# S206D.net
KiCad netlist of a schematic drawn in EAGLE
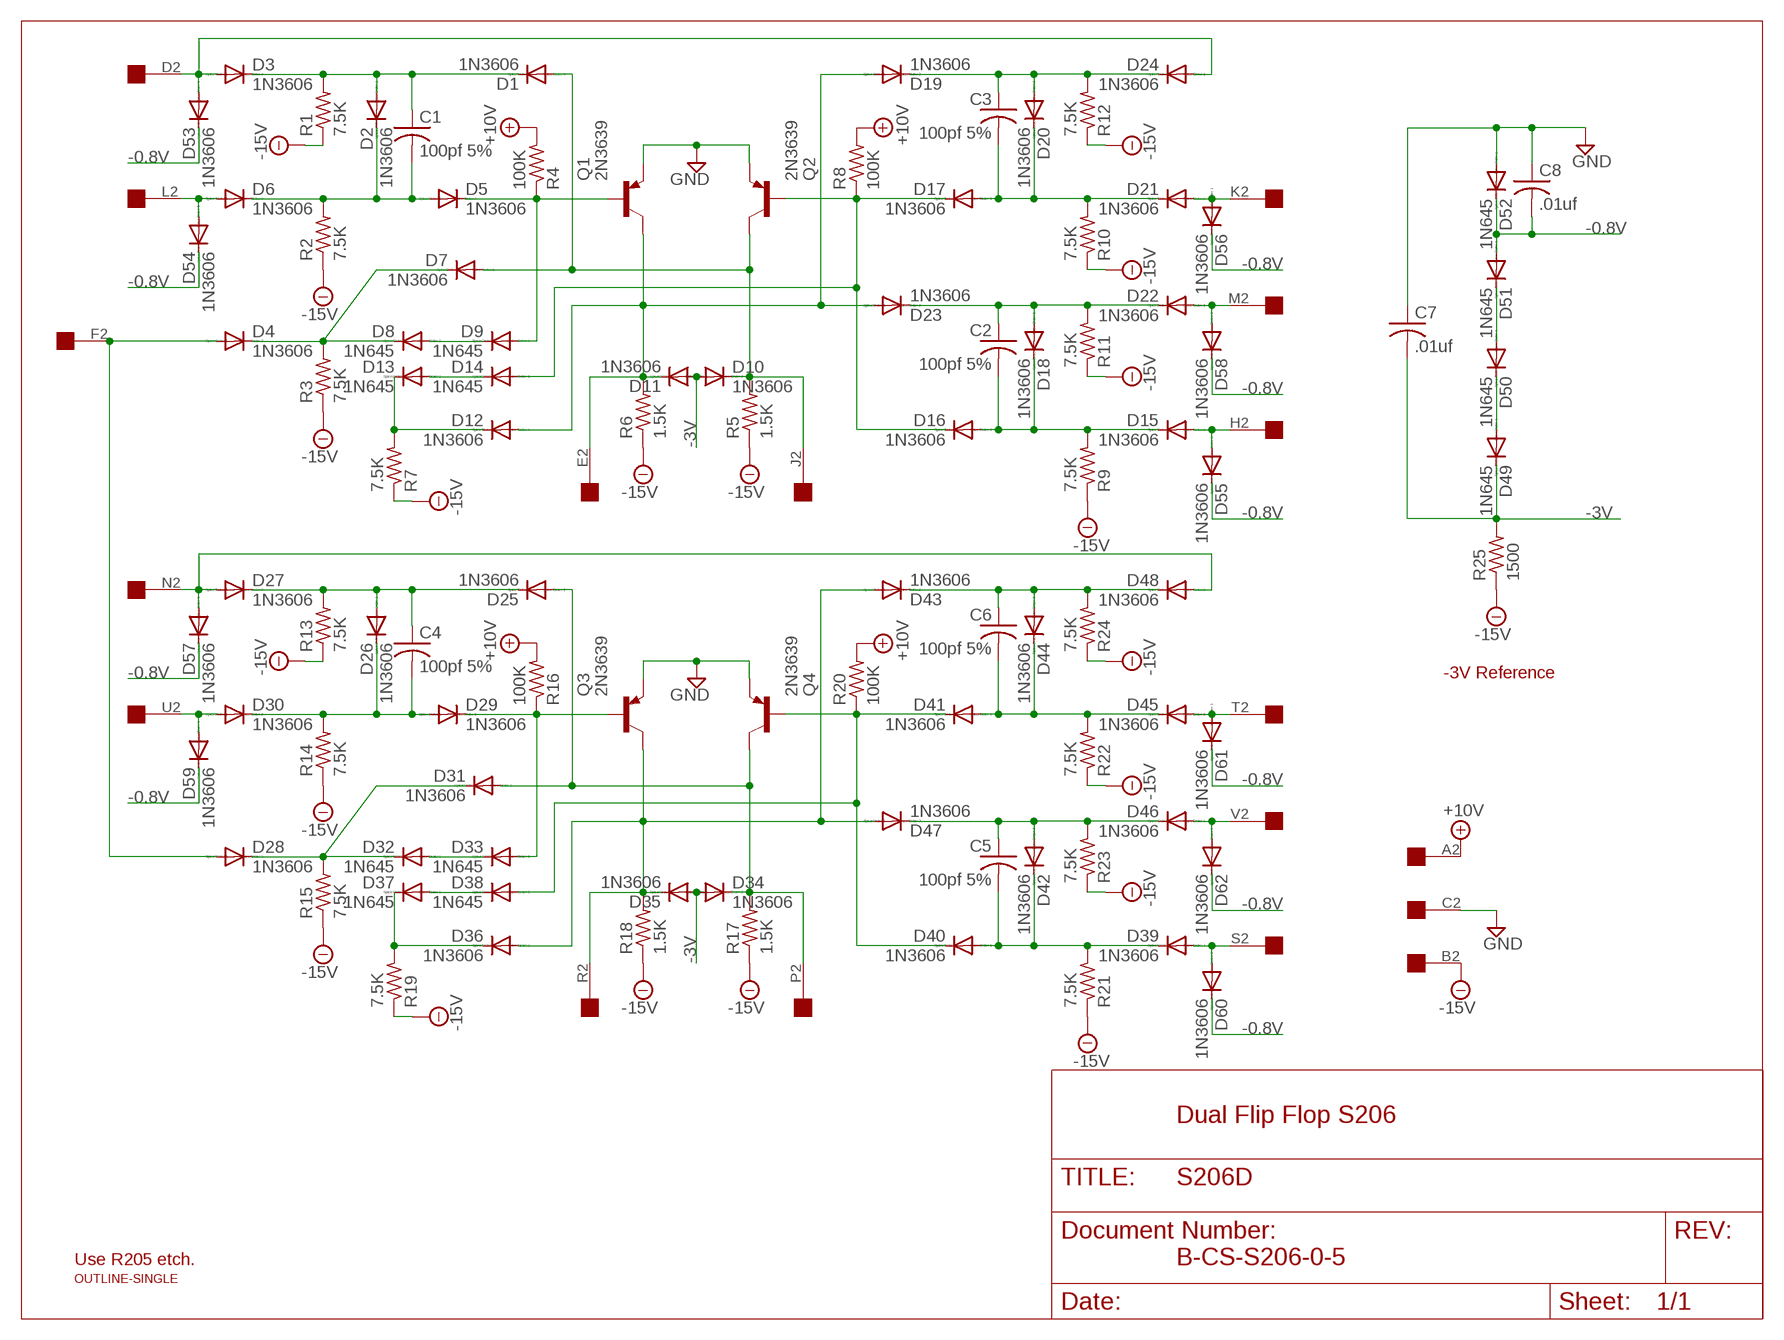
[diagram p0: schematic, sheet 1]

(export (version "E")
  (design (tool "Eeschema 10.0.6"))
  (components
    (comp (ref "C1")
      (value "100pf 5%")
      (footprint "eagle-import:C050-025X075")
      (libsource (lib "eagle-import") (part "C-US050-025X075"))
    )
    (comp (ref "C2")
      (value "100pf 5%")
      (footprint "eagle-import:C050-025X075")
      (libsource (lib "eagle-import") (part "C-US050-025X075"))
    )
    (comp (ref "C3")
      (value "100pf 5%")
      (footprint "eagle-import:C050-025X075")
      (libsource (lib "eagle-import") (part "C-US050-025X075"))
    )
    (comp (ref "C4")
      (value "100pf 5%")
      (footprint "eagle-import:C050-025X075")
      (libsource (lib "eagle-import") (part "C-US050-025X075"))
    )
    (comp (ref "C5")
      (value "100pf 5%")
      (footprint "eagle-import:C050-025X075")
      (libsource (lib "eagle-import") (part "C-US050-025X075"))
    )
    (comp (ref "C6")
      (value "100pf 5%")
      (footprint "eagle-import:C050-025X075")
      (libsource (lib "eagle-import") (part "C-US050-025X075"))
    )
    (comp (ref "C7")
      (value ".01uf")
      (footprint "eagle-import:C050-025X075")
      (libsource (lib "eagle-import") (part "C-US050-025X075"))
    )
    (comp (ref "C8")
      (value ".01uf")
      (footprint "eagle-import:C050-025X075")
      (libsource (lib "eagle-import") (part "C-US050-025X075"))
    )
    (comp (ref "D1")
      (value "1N3606")
      (footprint "eagle-import:DO35-10")
      (libsource (lib "eagle-import") (part "1N4148DO35-10"))
    )
    (comp (ref "D2")
      (value "1N3606")
      (footprint "eagle-import:DO35-10")
      (libsource (lib "eagle-import") (part "1N4148DO35-10"))
    )
    (comp (ref "D3")
      (value "1N3606")
      (footprint "eagle-import:DO35-10")
      (libsource (lib "eagle-import") (part "1N4148DO35-10"))
    )
    (comp (ref "D4")
      (value "1N3606")
      (footprint "eagle-import:DO35-10")
      (libsource (lib "eagle-import") (part "1N4148DO35-10"))
    )
    (comp (ref "D5")
      (value "1N3606")
      (footprint "eagle-import:DO35-10")
      (libsource (lib "eagle-import") (part "1N4148DO35-10"))
    )
    (comp (ref "D6")
      (value "1N3606")
      (footprint "eagle-import:DO35-10")
      (libsource (lib "eagle-import") (part "1N4148DO35-10"))
    )
    (comp (ref "D7")
      (value "1N3606")
      (footprint "eagle-import:DO35-10")
      (libsource (lib "eagle-import") (part "1N4148DO35-10"))
    )
    (comp (ref "D8")
      (value "1N645")
      (footprint "eagle-import:DO35-10")
      (libsource (lib "eagle-import") (part "1N4148DO35-10"))
    )
    (comp (ref "D9")
      (value "1N645")
      (footprint "eagle-import:DO35-10")
      (libsource (lib "eagle-import") (part "1N4148DO35-10"))
    )
    (comp (ref "D10")
      (value "1N3606")
      (footprint "eagle-import:DO35-10")
      (libsource (lib "eagle-import") (part "1N4148DO35-10"))
    )
    (comp (ref "D11")
      (value "1N3606")
      (footprint "eagle-import:DO35-10")
      (libsource (lib "eagle-import") (part "1N4148DO35-10"))
    )
    (comp (ref "D12")
      (value "1N3606")
      (footprint "eagle-import:DO35-10")
      (libsource (lib "eagle-import") (part "1N4148DO35-10"))
    )
    (comp (ref "D13")
      (value "1N645")
      (footprint "eagle-import:DO35-10")
      (libsource (lib "eagle-import") (part "1N4148DO35-10"))
    )
    (comp (ref "D14")
      (value "1N645")
      (footprint "eagle-import:DO35-10")
      (libsource (lib "eagle-import") (part "1N4148DO35-10"))
    )
    (comp (ref "D15")
      (value "1N3606")
      (footprint "eagle-import:DO35-10")
      (libsource (lib "eagle-import") (part "1N4148DO35-10"))
    )
    (comp (ref "D16")
      (value "1N3606")
      (footprint "eagle-import:DO35-10")
      (libsource (lib "eagle-import") (part "1N4148DO35-10"))
    )
    (comp (ref "D17")
      (value "1N3606")
      (footprint "eagle-import:DO35-10")
      (libsource (lib "eagle-import") (part "1N4148DO35-10"))
    )
    (comp (ref "D18")
      (value "1N3606")
      (footprint "eagle-import:DO35-10")
      (libsource (lib "eagle-import") (part "1N4148DO35-10"))
    )
    (comp (ref "D19")
      (value "1N3606")
      (footprint "eagle-import:DO35-10")
      (libsource (lib "eagle-import") (part "1N4148DO35-10"))
    )
    (comp (ref "D20")
      (value "1N3606")
      (footprint "eagle-import:DO35-10")
      (libsource (lib "eagle-import") (part "1N4148DO35-10"))
    )
    (comp (ref "D21")
      (value "1N3606")
      (footprint "eagle-import:DO35-10")
      (libsource (lib "eagle-import") (part "1N4148DO35-10"))
    )
    (comp (ref "D22")
      (value "1N3606")
      (footprint "eagle-import:DO35-10")
      (libsource (lib "eagle-import") (part "1N4148DO35-10"))
    )
    (comp (ref "D23")
      (value "1N3606")
      (footprint "eagle-import:DO35-10")
      (libsource (lib "eagle-import") (part "1N4148DO35-10"))
    )
    (comp (ref "D24")
      (value "1N3606")
      (footprint "eagle-import:DO35-10")
      (libsource (lib "eagle-import") (part "1N4148DO35-10"))
    )
    (comp (ref "D25")
      (value "1N3606")
      (footprint "eagle-import:DO35-10")
      (libsource (lib "eagle-import") (part "1N4148DO35-10"))
    )
    (comp (ref "D26")
      (value "1N3606")
      (footprint "eagle-import:DO35-10")
      (libsource (lib "eagle-import") (part "1N4148DO35-10"))
    )
    (comp (ref "D27")
      (value "1N3606")
      (footprint "eagle-import:DO35-10")
      (libsource (lib "eagle-import") (part "1N4148DO35-10"))
    )
    (comp (ref "D28")
      (value "1N3606")
      (footprint "eagle-import:DO35-10")
      (libsource (lib "eagle-import") (part "1N4148DO35-10"))
    )
    (comp (ref "D29")
      (value "1N3606")
      (footprint "eagle-import:DO35-10")
      (libsource (lib "eagle-import") (part "1N4148DO35-10"))
    )
    (comp (ref "D30")
      (value "1N3606")
      (footprint "eagle-import:DO35-10")
      (libsource (lib "eagle-import") (part "1N4148DO35-10"))
    )
    (comp (ref "D31")
      (value "1N3606")
      (footprint "eagle-import:DO35-10")
      (libsource (lib "eagle-import") (part "1N4148DO35-10"))
    )
    (comp (ref "D32")
      (value "1N645")
      (footprint "eagle-import:DO35-10")
      (libsource (lib "eagle-import") (part "1N4148DO35-10"))
    )
    (comp (ref "D33")
      (value "1N645")
      (footprint "eagle-import:DO35-10")
      (libsource (lib "eagle-import") (part "1N4148DO35-10"))
    )
    (comp (ref "D34")
      (value "1N3606")
      (footprint "eagle-import:DO35-10")
      (libsource (lib "eagle-import") (part "1N4148DO35-10"))
    )
    (comp (ref "D35")
      (value "1N3606")
      (footprint "eagle-import:DO35-10")
      (libsource (lib "eagle-import") (part "1N4148DO35-10"))
    )
    (comp (ref "D36")
      (value "1N3606")
      (footprint "eagle-import:DO35-10")
      (libsource (lib "eagle-import") (part "1N4148DO35-10"))
    )
    (comp (ref "D37")
      (value "1N645")
      (footprint "eagle-import:DO35-10")
      (libsource (lib "eagle-import") (part "1N4148DO35-10"))
    )
    (comp (ref "D38")
      (value "1N645")
      (footprint "eagle-import:DO35-10")
      (libsource (lib "eagle-import") (part "1N4148DO35-10"))
    )
    (comp (ref "D39")
      (value "1N3606")
      (footprint "eagle-import:DO35-10")
      (libsource (lib "eagle-import") (part "1N4148DO35-10"))
    )
    (comp (ref "D40")
      (value "1N3606")
      (footprint "eagle-import:DO35-10")
      (libsource (lib "eagle-import") (part "1N4148DO35-10"))
    )
    (comp (ref "D41")
      (value "1N3606")
      (footprint "eagle-import:DO35-10")
      (libsource (lib "eagle-import") (part "1N4148DO35-10"))
    )
    (comp (ref "D42")
      (value "1N3606")
      (footprint "eagle-import:DO35-10")
      (libsource (lib "eagle-import") (part "1N4148DO35-10"))
    )
    (comp (ref "D43")
      (value "1N3606")
      (footprint "eagle-import:DO35-10")
      (libsource (lib "eagle-import") (part "1N4148DO35-10"))
    )
    (comp (ref "D44")
      (value "1N3606")
      (footprint "eagle-import:DO35-10")
      (libsource (lib "eagle-import") (part "1N4148DO35-10"))
    )
    (comp (ref "D45")
      (value "1N3606")
      (footprint "eagle-import:DO35-10")
      (libsource (lib "eagle-import") (part "1N4148DO35-10"))
    )
    (comp (ref "D46")
      (value "1N3606")
      (footprint "eagle-import:DO35-10")
      (libsource (lib "eagle-import") (part "1N4148DO35-10"))
    )
    (comp (ref "D47")
      (value "1N3606")
      (footprint "eagle-import:DO35-10")
      (libsource (lib "eagle-import") (part "1N4148DO35-10"))
    )
    (comp (ref "D48")
      (value "1N3606")
      (footprint "eagle-import:DO35-10")
      (libsource (lib "eagle-import") (part "1N4148DO35-10"))
    )
    (comp (ref "D49")
      (value "1N645")
      (footprint "eagle-import:DO35-10")
      (libsource (lib "eagle-import") (part "1N4148DO35-10"))
    )
    (comp (ref "D50")
      (value "1N645")
      (footprint "eagle-import:DO35-10")
      (libsource (lib "eagle-import") (part "1N4148DO35-10"))
    )
    (comp (ref "D51")
      (value "1N645")
      (footprint "eagle-import:DO35-10")
      (libsource (lib "eagle-import") (part "1N4148DO35-10"))
    )
    (comp (ref "D52")
      (value "1N645")
      (footprint "eagle-import:DO35-10")
      (libsource (lib "eagle-import") (part "1N4148DO35-10"))
    )
    (comp (ref "D53")
      (value "1N3606")
      (footprint "eagle-import:DO35-10")
      (libsource (lib "eagle-import") (part "1N4148DO35-10"))
    )
    (comp (ref "D54")
      (value "1N3606")
      (footprint "eagle-import:DO35-10")
      (libsource (lib "eagle-import") (part "1N4148DO35-10"))
    )
    (comp (ref "D55")
      (value "1N3606")
      (footprint "eagle-import:DO35-10")
      (libsource (lib "eagle-import") (part "1N4148DO35-10"))
    )
    (comp (ref "D56")
      (value "1N3606")
      (footprint "eagle-import:DO35-10")
      (libsource (lib "eagle-import") (part "1N4148DO35-10"))
    )
    (comp (ref "D57")
      (value "1N3606")
      (footprint "eagle-import:DO35-10")
      (libsource (lib "eagle-import") (part "1N4148DO35-10"))
    )
    (comp (ref "D58")
      (value "1N3606")
      (footprint "eagle-import:DO35-10")
      (libsource (lib "eagle-import") (part "1N4148DO35-10"))
    )
    (comp (ref "D59")
      (value "1N3606")
      (footprint "eagle-import:DO35-10")
      (libsource (lib "eagle-import") (part "1N4148DO35-10"))
    )
    (comp (ref "D60")
      (value "1N3606")
      (footprint "eagle-import:DO35-10")
      (libsource (lib "eagle-import") (part "1N4148DO35-10"))
    )
    (comp (ref "D61")
      (value "1N3606")
      (footprint "eagle-import:DO35-10")
      (libsource (lib "eagle-import") (part "1N4148DO35-10"))
    )
    (comp (ref "D62")
      (value "1N3606")
      (footprint "eagle-import:DO35-10")
      (libsource (lib "eagle-import") (part "1N4148DO35-10"))
    )
    (comp (ref "Q1")
      (value "2N3639")
      (footprint "eagle-import:TO39")
      (libsource (lib "eagle-import") (part "2N3637"))
    )
    (comp (ref "Q2")
      (value "2N3639")
      (footprint "eagle-import:TO39")
      (libsource (lib "eagle-import") (part "2N3637"))
    )
    (comp (ref "Q3")
      (value "2N3639")
      (footprint "eagle-import:TO39")
      (libsource (lib "eagle-import") (part "2N3637"))
    )
    (comp (ref "Q4")
      (value "2N3639")
      (footprint "eagle-import:TO39")
      (libsource (lib "eagle-import") (part "2N3637"))
    )
    (comp (ref "R1")
      (value "7.5K")
      (footprint "eagle-import:0207_10")
      (libsource (lib "eagle-import") (part "R-US_0207/10"))
    )
    (comp (ref "R2")
      (value "7.5K")
      (footprint "eagle-import:0207_10")
      (libsource (lib "eagle-import") (part "R-US_0207/10"))
    )
    (comp (ref "R3")
      (value "7.5K")
      (footprint "eagle-import:0207_10")
      (libsource (lib "eagle-import") (part "R-US_0207/10"))
    )
    (comp (ref "R4")
      (value "100K")
      (footprint "eagle-import:0207_10")
      (libsource (lib "eagle-import") (part "R-US_0207/10"))
    )
    (comp (ref "R5")
      (value "1.5K")
      (footprint "eagle-import:0207_10")
      (libsource (lib "eagle-import") (part "R-US_0207/10"))
    )
    (comp (ref "R6")
      (value "1.5K")
      (footprint "eagle-import:0207_10")
      (libsource (lib "eagle-import") (part "R-US_0207/10"))
    )
    (comp (ref "R7")
      (value "7.5K")
      (footprint "eagle-import:0207_10")
      (libsource (lib "eagle-import") (part "R-US_0207/10"))
    )
    (comp (ref "R8")
      (value "100K")
      (footprint "eagle-import:0207_10")
      (libsource (lib "eagle-import") (part "R-US_0207/10"))
    )
    (comp (ref "R9")
      (value "7.5K")
      (footprint "eagle-import:0207_10")
      (libsource (lib "eagle-import") (part "R-US_0207/10"))
    )
    (comp (ref "R10")
      (value "7.5K")
      (footprint "eagle-import:0207_10")
      (libsource (lib "eagle-import") (part "R-US_0207/10"))
    )
    (comp (ref "R11")
      (value "7.5K")
      (footprint "eagle-import:0207_10")
      (libsource (lib "eagle-import") (part "R-US_0207/10"))
    )
    (comp (ref "R12")
      (value "7.5K")
      (footprint "eagle-import:0207_10")
      (libsource (lib "eagle-import") (part "R-US_0207/10"))
    )
    (comp (ref "R13")
      (value "7.5K")
      (footprint "eagle-import:0207_10")
      (libsource (lib "eagle-import") (part "R-US_0207/10"))
    )
    (comp (ref "R14")
      (value "7.5K")
      (footprint "eagle-import:0207_10")
      (libsource (lib "eagle-import") (part "R-US_0207/10"))
    )
    (comp (ref "R15")
      (value "7.5K")
      (footprint "eagle-import:0207_10")
      (libsource (lib "eagle-import") (part "R-US_0207/10"))
    )
    (comp (ref "R16")
      (value "100K")
      (footprint "eagle-import:0207_10")
      (libsource (lib "eagle-import") (part "R-US_0207/10"))
    )
    (comp (ref "R17")
      (value "1.5K")
      (footprint "eagle-import:0207_10")
      (libsource (lib "eagle-import") (part "R-US_0207/10"))
    )
    (comp (ref "R18")
      (value "1.5K")
      (footprint "eagle-import:0207_10")
      (libsource (lib "eagle-import") (part "R-US_0207/10"))
    )
    (comp (ref "R19")
      (value "7.5K")
      (footprint "eagle-import:0207_10")
      (libsource (lib "eagle-import") (part "R-US_0207/10"))
    )
    (comp (ref "R20")
      (value "100K")
      (footprint "eagle-import:0207_10")
      (libsource (lib "eagle-import") (part "R-US_0207/10"))
    )
    (comp (ref "R21")
      (value "7.5K")
      (footprint "eagle-import:0207_10")
      (libsource (lib "eagle-import") (part "R-US_0207/10"))
    )
    (comp (ref "R22")
      (value "7.5K")
      (footprint "eagle-import:0207_10")
      (libsource (lib "eagle-import") (part "R-US_0207/10"))
    )
    (comp (ref "R23")
      (value "7.5K")
      (footprint "eagle-import:0207_10")
      (libsource (lib "eagle-import") (part "R-US_0207/10"))
    )
    (comp (ref "R24")
      (value "7.5K")
      (footprint "eagle-import:0207_10")
      (libsource (lib "eagle-import") (part "R-US_0207/10"))
    )
    (comp (ref "R25")
      (value "1500")
      (footprint "eagle-import:0207_10")
      (libsource (lib "eagle-import") (part "R-US_0207/10"))
    )
    (comp (ref "U$1")
      (value "OUTLINE-SINGLE")
      (footprint "eagle-import:SINGLE")
      (libsource (lib "eagle-import") (part "OUTLINE-SINGLE"))
    )
    (comp (ref "U$2")
      (value "EDGE-1")
      (footprint "eagle-import:EDGE-CON1")
      (libsource (lib "eagle-import") (part "EDGE-1"))
    )
  )
  (nets
    (net (code "1") (name "+10V") (class "Default")
      (node (ref "R16") (pin "2") (pinfunction "2_2") (pintype "passive"))
      (node (ref "R20") (pin "2") (pinfunction "2_2") (pintype "passive"))
      (node (ref "R4") (pin "2") (pinfunction "2_2") (pintype "passive"))
      (node (ref "R8") (pin "2") (pinfunction "2_2") (pintype "passive"))
      (node (ref "U$2") (pin "A2") (pinfunction "1_A2") (pintype "bidirectional"))
    )
    (net (code "2") (name "-15V") (class "Default")
      (node (ref "R1") (pin "1") (pinfunction "1_1") (pintype "passive"))
      (node (ref "R10") (pin "1") (pinfunction "1_1") (pintype "passive"))
      (node (ref "R11") (pin "1") (pinfunction "1_1") (pintype "passive"))
      (node (ref "R12") (pin "1") (pinfunction "1_1") (pintype "passive"))
      (node (ref "R13") (pin "1") (pinfunction "1_1") (pintype "passive"))
      (node (ref "R14") (pin "1") (pinfunction "1_1") (pintype "passive"))
      (node (ref "R15") (pin "1") (pinfunction "1_1") (pintype "passive"))
      (node (ref "R17") (pin "1") (pinfunction "1_1") (pintype "passive"))
      (node (ref "R18") (pin "1") (pinfunction "1_1") (pintype "passive"))
      (node (ref "R19") (pin "1") (pinfunction "1_1") (pintype "passive"))
      (node (ref "R2") (pin "1") (pinfunction "1_1") (pintype "passive"))
      (node (ref "R21") (pin "1") (pinfunction "1_1") (pintype "passive"))
      (node (ref "R22") (pin "1") (pinfunction "1_1") (pintype "passive"))
      (node (ref "R23") (pin "1") (pinfunction "1_1") (pintype "passive"))
      (node (ref "R24") (pin "1") (pinfunction "1_1") (pintype "passive"))
      (node (ref "R25") (pin "1") (pinfunction "1_1") (pintype "passive"))
      (node (ref "R3") (pin "1") (pinfunction "1_1") (pintype "passive"))
      (node (ref "R5") (pin "1") (pinfunction "1_1") (pintype "passive"))
      (node (ref "R6") (pin "1") (pinfunction "1_1") (pintype "passive"))
      (node (ref "R7") (pin "1") (pinfunction "1_1") (pintype "passive"))
      (node (ref "R9") (pin "1") (pinfunction "1_1") (pintype "passive"))
      (node (ref "U$2") (pin "B2") (pinfunction "1_B2") (pintype "bidirectional"))
    )
    (net (code "3") (name "/-0.8V") (class "Default")
      (node (ref "C8") (pin "2") (pinfunction "2_2") (pintype "passive"))
      (node (ref "D51") (pin "A") (pinfunction "A_A") (pintype "passive"))
      (node (ref "D52") (pin "C") (pinfunction "C_C") (pintype "passive"))
      (node (ref "D53") (pin "C") (pinfunction "C_C") (pintype "passive"))
      (node (ref "D54") (pin "C") (pinfunction "C_C") (pintype "passive"))
      (node (ref "D55") (pin "C") (pinfunction "C_C") (pintype "passive"))
      (node (ref "D56") (pin "C") (pinfunction "C_C") (pintype "passive"))
      (node (ref "D57") (pin "C") (pinfunction "C_C") (pintype "passive"))
      (node (ref "D58") (pin "C") (pinfunction "C_C") (pintype "passive"))
      (node (ref "D59") (pin "C") (pinfunction "C_C") (pintype "passive"))
      (node (ref "D60") (pin "C") (pinfunction "C_C") (pintype "passive"))
      (node (ref "D61") (pin "C") (pinfunction "C_C") (pintype "passive"))
      (node (ref "D62") (pin "C") (pinfunction "C_C") (pintype "passive"))
    )
    (net (code "4") (name "/-3V") (class "Default")
      (node (ref "C7") (pin "2") (pinfunction "2_2") (pintype "passive"))
      (node (ref "D10") (pin "A") (pinfunction "A_A") (pintype "passive"))
      (node (ref "D11") (pin "A") (pinfunction "A_A") (pintype "passive"))
      (node (ref "D34") (pin "A") (pinfunction "A_A") (pintype "passive"))
      (node (ref "D35") (pin "A") (pinfunction "A_A") (pintype "passive"))
      (node (ref "D49") (pin "C") (pinfunction "C_C") (pintype "passive"))
      (node (ref "R25") (pin "2") (pinfunction "2_2") (pintype "passive"))
    )
    (net (code "5") (name "GND") (class "Default")
      (node (ref "C7") (pin "1") (pinfunction "1_1") (pintype "passive"))
      (node (ref "C8") (pin "1") (pinfunction "1_1") (pintype "passive"))
      (node (ref "D52") (pin "A") (pinfunction "A_A") (pintype "passive"))
      (node (ref "Q1") (pin "1") (pinfunction "E_1") (pintype "passive"))
      (node (ref "Q2") (pin "1") (pinfunction "E_1") (pintype "passive"))
      (node (ref "Q3") (pin "1") (pinfunction "E_1") (pintype "passive"))
      (node (ref "Q4") (pin "1") (pinfunction "E_1") (pintype "passive"))
      (node (ref "U$2") (pin "C2") (pinfunction "1_C2") (pintype "bidirectional"))
    )
    (net (code "6") (name "Net-(C1-Pad1)") (class "Default")
      (node (ref "C1") (pin "1") (pinfunction "1_1") (pintype "passive"))
      (node (ref "D1") (pin "C") (pinfunction "C_C") (pintype "passive"))
      (node (ref "D2") (pin "A") (pinfunction "A_A") (pintype "passive"))
      (node (ref "D3") (pin "C") (pinfunction "C_C") (pintype "passive"))
      (node (ref "R1") (pin "2") (pinfunction "2_2") (pintype "passive"))
    )
    (net (code "7") (name "Net-(C1-Pad2)") (class "Default")
      (node (ref "C1") (pin "2") (pinfunction "2_2") (pintype "passive"))
      (node (ref "D2") (pin "C") (pinfunction "C_C") (pintype "passive"))
      (node (ref "D5") (pin "A") (pinfunction "A_A") (pintype "passive"))
      (node (ref "D6") (pin "C") (pinfunction "C_C") (pintype "passive"))
      (node (ref "R2") (pin "2") (pinfunction "2_2") (pintype "passive"))
    )
    (net (code "8") (name "Net-(C2-Pad1)") (class "Default")
      (node (ref "C2") (pin "1") (pinfunction "1_1") (pintype "passive"))
      (node (ref "D18") (pin "A") (pinfunction "A_A") (pintype "passive"))
      (node (ref "D22") (pin "C") (pinfunction "C_C") (pintype "passive"))
      (node (ref "D23") (pin "C") (pinfunction "C_C") (pintype "passive"))
      (node (ref "R11") (pin "2") (pinfunction "2_2") (pintype "passive"))
    )
    (net (code "9") (name "Net-(C2-Pad2)") (class "Default")
      (node (ref "C2") (pin "2") (pinfunction "2_2") (pintype "passive"))
      (node (ref "D15") (pin "C") (pinfunction "C_C") (pintype "passive"))
      (node (ref "D16") (pin "A") (pinfunction "A_A") (pintype "passive"))
      (node (ref "D18") (pin "C") (pinfunction "C_C") (pintype "passive"))
      (node (ref "R9") (pin "2") (pinfunction "2_2") (pintype "passive"))
    )
    (net (code "10") (name "Net-(C3-Pad1)") (class "Default")
      (node (ref "C3") (pin "1") (pinfunction "1_1") (pintype "passive"))
      (node (ref "D19") (pin "C") (pinfunction "C_C") (pintype "passive"))
      (node (ref "D20") (pin "A") (pinfunction "A_A") (pintype "passive"))
      (node (ref "D24") (pin "C") (pinfunction "C_C") (pintype "passive"))
      (node (ref "R12") (pin "2") (pinfunction "2_2") (pintype "passive"))
    )
    (net (code "11") (name "Net-(C3-Pad2)") (class "Default")
      (node (ref "C3") (pin "2") (pinfunction "2_2") (pintype "passive"))
      (node (ref "D17") (pin "A") (pinfunction "A_A") (pintype "passive"))
      (node (ref "D20") (pin "C") (pinfunction "C_C") (pintype "passive"))
      (node (ref "D21") (pin "C") (pinfunction "C_C") (pintype "passive"))
      (node (ref "R10") (pin "2") (pinfunction "2_2") (pintype "passive"))
    )
    (net (code "12") (name "Net-(C4-Pad1)") (class "Default")
      (node (ref "C4") (pin "1") (pinfunction "1_1") (pintype "passive"))
      (node (ref "D25") (pin "C") (pinfunction "C_C") (pintype "passive"))
      (node (ref "D26") (pin "A") (pinfunction "A_A") (pintype "passive"))
      (node (ref "D27") (pin "C") (pinfunction "C_C") (pintype "passive"))
      (node (ref "R13") (pin "2") (pinfunction "2_2") (pintype "passive"))
    )
    (net (code "13") (name "Net-(C4-Pad2)") (class "Default")
      (node (ref "C4") (pin "2") (pinfunction "2_2") (pintype "passive"))
      (node (ref "D26") (pin "C") (pinfunction "C_C") (pintype "passive"))
      (node (ref "D29") (pin "A") (pinfunction "A_A") (pintype "passive"))
      (node (ref "D30") (pin "C") (pinfunction "C_C") (pintype "passive"))
      (node (ref "R14") (pin "2") (pinfunction "2_2") (pintype "passive"))
    )
    (net (code "14") (name "Net-(C5-Pad1)") (class "Default")
      (node (ref "C5") (pin "1") (pinfunction "1_1") (pintype "passive"))
      (node (ref "D42") (pin "A") (pinfunction "A_A") (pintype "passive"))
      (node (ref "D46") (pin "C") (pinfunction "C_C") (pintype "passive"))
      (node (ref "D47") (pin "C") (pinfunction "C_C") (pintype "passive"))
      (node (ref "R23") (pin "2") (pinfunction "2_2") (pintype "passive"))
    )
    (net (code "15") (name "Net-(C5-Pad2)") (class "Default")
      (node (ref "C5") (pin "2") (pinfunction "2_2") (pintype "passive"))
      (node (ref "D39") (pin "C") (pinfunction "C_C") (pintype "passive"))
      (node (ref "D40") (pin "A") (pinfunction "A_A") (pintype "passive"))
      (node (ref "D42") (pin "C") (pinfunction "C_C") (pintype "passive"))
      (node (ref "R21") (pin "2") (pinfunction "2_2") (pintype "passive"))
    )
    (net (code "16") (name "Net-(C6-Pad1)") (class "Default")
      (node (ref "C6") (pin "1") (pinfunction "1_1") (pintype "passive"))
      (node (ref "D43") (pin "C") (pinfunction "C_C") (pintype "passive"))
      (node (ref "D44") (pin "A") (pinfunction "A_A") (pintype "passive"))
      (node (ref "D48") (pin "C") (pinfunction "C_C") (pintype "passive"))
      (node (ref "R24") (pin "2") (pinfunction "2_2") (pintype "passive"))
    )
    (net (code "17") (name "Net-(C6-Pad2)") (class "Default")
      (node (ref "C6") (pin "2") (pinfunction "2_2") (pintype "passive"))
      (node (ref "D41") (pin "A") (pinfunction "A_A") (pintype "passive"))
      (node (ref "D44") (pin "C") (pinfunction "C_C") (pintype "passive"))
      (node (ref "D45") (pin "C") (pinfunction "C_C") (pintype "passive"))
      (node (ref "R22") (pin "2") (pinfunction "2_2") (pintype "passive"))
    )
    (net (code "18") (name "Net-(D4-PadC)") (class "Default")
      (node (ref "D4") (pin "C") (pinfunction "C_C") (pintype "passive"))
      (node (ref "D7") (pin "C") (pinfunction "C_C") (pintype "passive"))
      (node (ref "D8") (pin "C") (pinfunction "C_C") (pintype "passive"))
      (node (ref "R3") (pin "2") (pinfunction "2_2") (pintype "passive"))
    )
    (net (code "19") (name "Net-(D8-PadA)") (class "Default")
      (node (ref "D8") (pin "A") (pinfunction "A_A") (pintype "passive"))
      (node (ref "D9") (pin "C") (pinfunction "C_C") (pintype "passive"))
    )
    (net (code "20") (name "Net-(D12-PadC)") (class "Default")
      (node (ref "D12") (pin "C") (pinfunction "C_C") (pintype "passive"))
      (node (ref "D13") (pin "C") (pinfunction "C_C") (pintype "passive"))
      (node (ref "R7") (pin "2") (pinfunction "2_2") (pintype "passive"))
    )
    (net (code "21") (name "Net-(D13-PadA)") (class "Default")
      (node (ref "D13") (pin "A") (pinfunction "A_A") (pintype "passive"))
      (node (ref "D14") (pin "C") (pinfunction "C_C") (pintype "passive"))
    )
    (net (code "22") (name "Net-(D28-PadC)") (class "Default")
      (node (ref "D28") (pin "C") (pinfunction "C_C") (pintype "passive"))
      (node (ref "D31") (pin "C") (pinfunction "C_C") (pintype "passive"))
      (node (ref "D32") (pin "C") (pinfunction "C_C") (pintype "passive"))
      (node (ref "R15") (pin "2") (pinfunction "2_2") (pintype "passive"))
    )
    (net (code "23") (name "Net-(D32-PadA)") (class "Default")
      (node (ref "D32") (pin "A") (pinfunction "A_A") (pintype "passive"))
      (node (ref "D33") (pin "C") (pinfunction "C_C") (pintype "passive"))
    )
    (net (code "24") (name "Net-(D36-PadC)") (class "Default")
      (node (ref "D36") (pin "C") (pinfunction "C_C") (pintype "passive"))
      (node (ref "D37") (pin "C") (pinfunction "C_C") (pintype "passive"))
      (node (ref "R19") (pin "2") (pinfunction "2_2") (pintype "passive"))
    )
    (net (code "25") (name "Net-(D37-PadA)") (class "Default")
      (node (ref "D37") (pin "A") (pinfunction "A_A") (pintype "passive"))
      (node (ref "D38") (pin "C") (pinfunction "C_C") (pintype "passive"))
    )
    (net (code "26") (name "Net-(D49-PadA)") (class "Default")
      (node (ref "D49") (pin "A") (pinfunction "A_A") (pintype "passive"))
      (node (ref "D50") (pin "C") (pinfunction "C_C") (pintype "passive"))
    )
    (net (code "27") (name "Net-(D50-PadA)") (class "Default")
      (node (ref "D50") (pin "A") (pinfunction "A_A") (pintype "passive"))
      (node (ref "D51") (pin "C") (pinfunction "C_C") (pintype "passive"))
    )
    (net (code "28") (name "Net-(Q1-B)") (class "Default")
      (node (ref "D5") (pin "C") (pinfunction "C_C") (pintype "passive"))
      (node (ref "D9") (pin "A") (pinfunction "A_A") (pintype "passive"))
      (node (ref "Q1") (pin "2") (pinfunction "B_2") (pintype "passive"))
      (node (ref "R4") (pin "1") (pinfunction "1_1") (pintype "passive"))
    )
    (net (code "29") (name "Net-(Q1-C)") (class "Default")
      (node (ref "D11") (pin "C") (pinfunction "C_C") (pintype "passive"))
      (node (ref "D12") (pin "A") (pinfunction "A_A") (pintype "passive"))
      (node (ref "D19") (pin "A") (pinfunction "A_A") (pintype "passive"))
      (node (ref "D23") (pin "A") (pinfunction "A_A") (pintype "passive"))
      (node (ref "Q1") (pin "3") (pinfunction "C_3") (pintype "passive"))
      (node (ref "R6") (pin "2") (pinfunction "2_2") (pintype "passive"))
      (node (ref "U$2") (pin "E2") (pinfunction "1_E2") (pintype "bidirectional"))
    )
    (net (code "30") (name "Net-(Q2-B)") (class "Default")
      (node (ref "D14") (pin "A") (pinfunction "A_A") (pintype "passive"))
      (node (ref "D16") (pin "C") (pinfunction "C_C") (pintype "passive"))
      (node (ref "D17") (pin "C") (pinfunction "C_C") (pintype "passive"))
      (node (ref "Q2") (pin "2") (pinfunction "B_2") (pintype "passive"))
      (node (ref "R8") (pin "1") (pinfunction "1_1") (pintype "passive"))
    )
    (net (code "31") (name "Net-(Q2-C)") (class "Default")
      (node (ref "D1") (pin "A") (pinfunction "A_A") (pintype "passive"))
      (node (ref "D10") (pin "C") (pinfunction "C_C") (pintype "passive"))
      (node (ref "D7") (pin "A") (pinfunction "A_A") (pintype "passive"))
      (node (ref "Q2") (pin "3") (pinfunction "C_3") (pintype "passive"))
      (node (ref "R5") (pin "2") (pinfunction "2_2") (pintype "passive"))
      (node (ref "U$2") (pin "J2") (pinfunction "1_J2") (pintype "bidirectional"))
    )
    (net (code "32") (name "Net-(Q3-B)") (class "Default")
      (node (ref "D29") (pin "C") (pinfunction "C_C") (pintype "passive"))
      (node (ref "D33") (pin "A") (pinfunction "A_A") (pintype "passive"))
      (node (ref "Q3") (pin "2") (pinfunction "B_2") (pintype "passive"))
      (node (ref "R16") (pin "1") (pinfunction "1_1") (pintype "passive"))
    )
    (net (code "33") (name "Net-(Q3-C)") (class "Default")
      (node (ref "D35") (pin "C") (pinfunction "C_C") (pintype "passive"))
      (node (ref "D36") (pin "A") (pinfunction "A_A") (pintype "passive"))
      (node (ref "D43") (pin "A") (pinfunction "A_A") (pintype "passive"))
      (node (ref "D47") (pin "A") (pinfunction "A_A") (pintype "passive"))
      (node (ref "Q3") (pin "3") (pinfunction "C_3") (pintype "passive"))
      (node (ref "R18") (pin "2") (pinfunction "2_2") (pintype "passive"))
      (node (ref "U$2") (pin "R2") (pinfunction "1_R2") (pintype "bidirectional"))
    )
    (net (code "34") (name "Net-(Q4-B)") (class "Default")
      (node (ref "D38") (pin "A") (pinfunction "A_A") (pintype "passive"))
      (node (ref "D40") (pin "C") (pinfunction "C_C") (pintype "passive"))
      (node (ref "D41") (pin "C") (pinfunction "C_C") (pintype "passive"))
      (node (ref "Q4") (pin "2") (pinfunction "B_2") (pintype "passive"))
      (node (ref "R20") (pin "1") (pinfunction "1_1") (pintype "passive"))
    )
    (net (code "35") (name "Net-(Q4-C)") (class "Default")
      (node (ref "D25") (pin "A") (pinfunction "A_A") (pintype "passive"))
      (node (ref "D31") (pin "A") (pinfunction "A_A") (pintype "passive"))
      (node (ref "D34") (pin "C") (pinfunction "C_C") (pintype "passive"))
      (node (ref "Q4") (pin "3") (pinfunction "C_3") (pintype "passive"))
      (node (ref "R17") (pin "2") (pinfunction "2_2") (pintype "passive"))
      (node (ref "U$2") (pin "P2") (pinfunction "1_P2") (pintype "bidirectional"))
    )
    (net (code "36") (name "Net-(U$2D-1)") (class "Default")
      (node (ref "D24") (pin "A") (pinfunction "A_A") (pintype "passive"))
      (node (ref "D3") (pin "A") (pinfunction "A_A") (pintype "passive"))
      (node (ref "D53") (pin "A") (pinfunction "A_A") (pintype "passive"))
      (node (ref "U$2") (pin "D2") (pinfunction "1_D2") (pintype "bidirectional"))
    )
    (net (code "37") (name "Net-(U$2F-1)") (class "Default")
      (node (ref "D28") (pin "A") (pinfunction "A_A") (pintype "passive"))
      (node (ref "D4") (pin "A") (pinfunction "A_A") (pintype "passive"))
      (node (ref "U$2") (pin "F2") (pinfunction "1_F2") (pintype "bidirectional"))
    )
    (net (code "38") (name "Net-(U$2G-1)") (class "Default")
      (node (ref "D15") (pin "A") (pinfunction "A_A") (pintype "passive"))
      (node (ref "D55") (pin "A") (pinfunction "A_A") (pintype "passive"))
      (node (ref "U$2") (pin "H2") (pinfunction "1_H2") (pintype "bidirectional"))
    )
    (net (code "39") (name "Net-(U$2I-1)") (class "Default")
      (node (ref "D21") (pin "A") (pinfunction "A_A") (pintype "passive"))
      (node (ref "D56") (pin "A") (pinfunction "A_A") (pintype "passive"))
      (node (ref "U$2") (pin "K2") (pinfunction "1_K2") (pintype "bidirectional"))
    )
    (net (code "40") (name "Net-(U$2J-1)") (class "Default")
      (node (ref "D54") (pin "A") (pinfunction "A_A") (pintype "passive"))
      (node (ref "D6") (pin "A") (pinfunction "A_A") (pintype "passive"))
      (node (ref "U$2") (pin "L2") (pinfunction "1_L2") (pintype "bidirectional"))
    )
    (net (code "41") (name "Net-(U$2K-1)") (class "Default")
      (node (ref "D22") (pin "A") (pinfunction "A_A") (pintype "passive"))
      (node (ref "D58") (pin "A") (pinfunction "A_A") (pintype "passive"))
      (node (ref "U$2") (pin "M2") (pinfunction "1_M2") (pintype "bidirectional"))
    )
    (net (code "42") (name "Net-(U$2L-1)") (class "Default")
      (node (ref "D27") (pin "A") (pinfunction "A_A") (pintype "passive"))
      (node (ref "D48") (pin "A") (pinfunction "A_A") (pintype "passive"))
      (node (ref "D57") (pin "A") (pinfunction "A_A") (pintype "passive"))
      (node (ref "U$2") (pin "N2") (pinfunction "1_N2") (pintype "bidirectional"))
    )
    (net (code "43") (name "Net-(U$2O-1)") (class "Default")
      (node (ref "D39") (pin "A") (pinfunction "A_A") (pintype "passive"))
      (node (ref "D60") (pin "A") (pinfunction "A_A") (pintype "passive"))
      (node (ref "U$2") (pin "S2") (pinfunction "1_S2") (pintype "bidirectional"))
    )
    (net (code "44") (name "Net-(U$2P-1)") (class "Default")
      (node (ref "D45") (pin "A") (pinfunction "A_A") (pintype "passive"))
      (node (ref "D61") (pin "A") (pinfunction "A_A") (pintype "passive"))
      (node (ref "U$2") (pin "T2") (pinfunction "1_T2") (pintype "bidirectional"))
    )
    (net (code "45") (name "Net-(U$2Q-1)") (class "Default")
      (node (ref "D30") (pin "A") (pinfunction "A_A") (pintype "passive"))
      (node (ref "D59") (pin "A") (pinfunction "A_A") (pintype "passive"))
      (node (ref "U$2") (pin "U2") (pinfunction "1_U2") (pintype "bidirectional"))
    )
    (net (code "46") (name "Net-(U$2R-1)") (class "Default")
      (node (ref "D46") (pin "A") (pinfunction "A_A") (pintype "passive"))
      (node (ref "D62") (pin "A") (pinfunction "A_A") (pintype "passive"))
      (node (ref "U$2") (pin "V2") (pinfunction "1_V2") (pintype "bidirectional"))
    )
  )
)
